# COMPASS_3_AXIS.net
KiCad netlist of a schematic drawn in Altium Designer
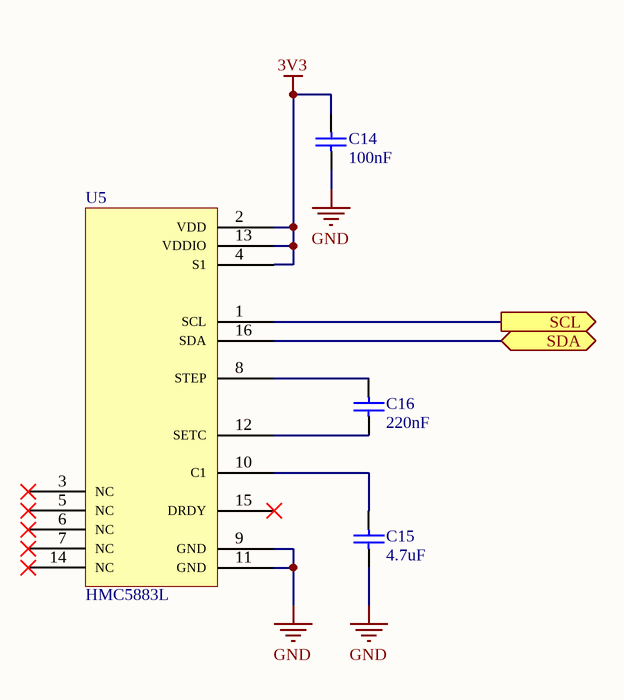
[diagram p0: COMPASS 3 AXIS.SchDoc]

(export (version "E")
  (design (tool "Eeschema 10.0.6"))
  (components
    (comp (ref "C14")
      (value "100nF")
      (footprint "C0603(1608)")
      (description "Capacitor")
      (libsource (lib "Miscellaneous Devices") (part "Cap"))
    )
    (comp (ref "C15")
      (value "4.7uF")
      (footprint "C0603(1608)")
      (description "Capacitor")
      (libsource (lib "Miscellaneous Devices") (part "Cap"))
    )
    (comp (ref "C16")
      (value "220nF")
      (footprint "C0603(1608)")
      (description "Capacitor")
      (libsource (lib "Miscellaneous Devices") (part "Cap"))
    )
    (comp (ref "U5")
      (value "HMC5883L")
      (footprint "LGA 16 - 3x3")
      (description "IC COMPASS 3 AXIS I2C 16LCC SMD")
      (libsource (lib "Flight_Controller") (part "HMC5883L"))
    )
  )
  (nets
    (net (code "1") (name "/SCL") (class "Default")
      (node (ref "U5") (pin "1") (pinfunction "SCL_1") (pintype "passive"))
    )
    (net (code "2") (name "/SDA") (class "Default")
      (node (ref "U5") (pin "16") (pinfunction "SDA_16") (pintype "passive"))
    )
    (net (code "3") (name "3V3") (class "Default")
      (node (ref "C14") (pin "2") (pinfunction "2_2") (pintype "passive"))
      (node (ref "U5") (pin "13") (pinfunction "VDDIO_13") (pintype "passive"))
      (node (ref "U5") (pin "2") (pinfunction "VDD_2") (pintype "passive"))
      (node (ref "U5") (pin "4") (pinfunction "S1_4") (pintype "passive"))
    )
    (net (code "4") (name "GND") (class "Default")
      (node (ref "C14") (pin "1") (pinfunction "1_1") (pintype "passive"))
      (node (ref "C15") (pin "1") (pinfunction "1_1") (pintype "passive"))
      (node (ref "U5") (pin "11") (pinfunction "GND_11") (pintype "passive"))
      (node (ref "U5") (pin "9") (pinfunction "GND_9") (pintype "passive"))
    )
    (net (code "5") (name "Net-(U5-C1)") (class "Default")
      (node (ref "C15") (pin "2") (pinfunction "2_2") (pintype "passive"))
      (node (ref "U5") (pin "10") (pinfunction "C1_10") (pintype "passive"))
    )
    (net (code "6") (name "Net-(U5-SETC)") (class "Default")
      (node (ref "C16") (pin "2") (pinfunction "2_2") (pintype "passive"))
      (node (ref "U5") (pin "12") (pinfunction "SETC_12") (pintype "passive"))
    )
    (net (code "7") (name "Net-(U5-STEP)") (class "Default")
      (node (ref "C16") (pin "1") (pinfunction "1_1") (pintype "passive"))
      (node (ref "U5") (pin "8") (pinfunction "STEP_8") (pintype "passive"))
    )
    (net (code "8") (name "unconnected-(U5-DRDY-Pad15)") (class "Default")
      (node (ref "U5") (pin "15") (pinfunction "DRDY_15") (pintype "passive+no_connect"))
    )
    (net (code "9") (name "unconnected-(U5-NC-Pad3)") (class "Default")
      (node (ref "U5") (pin "3") (pinfunction "NC_3") (pintype "passive+no_connect"))
    )
    (net (code "10") (name "unconnected-(U5-NC-Pad5)") (class "Default")
      (node (ref "U5") (pin "5") (pinfunction "NC_5") (pintype "passive+no_connect"))
    )
    (net (code "11") (name "unconnected-(U5-NC-Pad6)") (class "Default")
      (node (ref "U5") (pin "6") (pinfunction "NC_6") (pintype "passive+no_connect"))
    )
    (net (code "12") (name "unconnected-(U5-NC-Pad7)") (class "Default")
      (node (ref "U5") (pin "7") (pinfunction "NC_7") (pintype "passive+no_connect"))
    )
    (net (code "13") (name "unconnected-(U5-NC-Pad14)") (class "Default")
      (node (ref "U5") (pin "14") (pinfunction "NC_14") (pintype "passive+no_connect"))
    )
  )
)
